# tinypico-fc.net
KiCad netlist of a schematic drawn in EAGLE
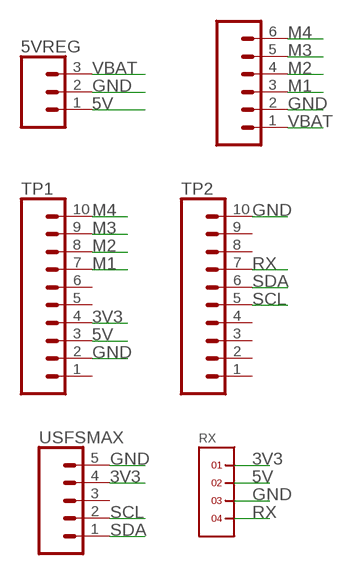
[diagram p0: schematic, sheet 1]

(export (version "E")
  (design (tool "Eeschema 10.0.6"))
  (components
    (comp (ref "5VREG")
      (value "CONN_031X03_NO_SILK")
      (footprint "eagle-import:1X03_NO_SILK")
      (libsource (lib "eagle-import") (part "CONN_031X03_NO_SILK"))
    )
    (comp (ref "ESC")
      (value "CONN_06NO_SILK_FEMALE_PTH")
      (footprint "eagle-import:1X06_NO_SILK")
      (libsource (lib "eagle-import") (part "CONN_06NO_SILK_FEMALE_PTH"))
    )
    (comp (ref "RX")
      (value "1X4")
      (footprint "eagle-import:1X4")
      (libsource (lib "eagle-import") (part "1X4"))
    )
    (comp (ref "TP1")
      (value "CONN_10NO_SILK_PTH_FEMALE")
      (footprint "eagle-import:1X10_NO_SILK")
      (libsource (lib "eagle-import") (part "CONN_10NO_SILK_PTH_FEMALE"))
    )
    (comp (ref "TP2")
      (value "CONN_10NO_SILK_PTH_FEMALE")
      (footprint "eagle-import:1X10_NO_SILK")
      (libsource (lib "eagle-import") (part "CONN_10NO_SILK_PTH_FEMALE"))
    )
    (comp (ref "USFSMAX")
      (value "CONN_05NO_SILK")
      (footprint "eagle-import:1X05_NO_SILK")
      (libsource (lib "eagle-import") (part "CONN_05NO_SILK"))
    )
  )
  (nets
    (net (code "1") (name "/3V3") (class "Default")
      (node (ref "RX") (pin "1") (pinfunction "1_1") (pintype "bidirectional"))
      (node (ref "TP1") (pin "4") (pinfunction "4_4") (pintype "passive"))
      (node (ref "USFSMAX") (pin "4") (pinfunction "4_4") (pintype "passive"))
    )
    (net (code "2") (name "/5V") (class "Default")
      (node (ref "5VREG") (pin "1") (pinfunction "1_1") (pintype "passive"))
      (node (ref "RX") (pin "2") (pinfunction "2_2") (pintype "bidirectional"))
      (node (ref "TP1") (pin "3") (pinfunction "3_3") (pintype "passive"))
    )
    (net (code "3") (name "/GND") (class "Default")
      (node (ref "5VREG") (pin "2") (pinfunction "2_2") (pintype "passive"))
      (node (ref "ESC") (pin "2") (pinfunction "2_2") (pintype "passive"))
      (node (ref "RX") (pin "3") (pinfunction "3_3") (pintype "bidirectional"))
      (node (ref "TP1") (pin "2") (pinfunction "2_2") (pintype "passive"))
      (node (ref "TP2") (pin "10") (pinfunction "10_10") (pintype "passive"))
      (node (ref "USFSMAX") (pin "5") (pinfunction "5_5") (pintype "passive"))
    )
    (net (code "4") (name "/M1") (class "Default")
      (node (ref "ESC") (pin "3") (pinfunction "3_3") (pintype "passive"))
      (node (ref "TP1") (pin "7") (pinfunction "7_7") (pintype "passive"))
    )
    (net (code "5") (name "/M2") (class "Default")
      (node (ref "ESC") (pin "4") (pinfunction "4_4") (pintype "passive"))
      (node (ref "TP1") (pin "8") (pinfunction "8_8") (pintype "passive"))
    )
    (net (code "6") (name "/M3") (class "Default")
      (node (ref "ESC") (pin "5") (pinfunction "5_5") (pintype "passive"))
      (node (ref "TP1") (pin "9") (pinfunction "9_9") (pintype "passive"))
    )
    (net (code "7") (name "/M4") (class "Default")
      (node (ref "ESC") (pin "6") (pinfunction "6_6") (pintype "passive"))
      (node (ref "TP1") (pin "10") (pinfunction "10_10") (pintype "passive"))
    )
    (net (code "8") (name "/RX") (class "Default")
      (node (ref "RX") (pin "4") (pinfunction "4_4") (pintype "bidirectional"))
      (node (ref "TP2") (pin "7") (pinfunction "7_7") (pintype "passive"))
    )
    (net (code "9") (name "/SCL") (class "Default")
      (node (ref "TP2") (pin "5") (pinfunction "5_5") (pintype "passive"))
      (node (ref "USFSMAX") (pin "2") (pinfunction "2_2") (pintype "passive"))
    )
    (net (code "10") (name "/SDA") (class "Default")
      (node (ref "TP2") (pin "6") (pinfunction "6_6") (pintype "passive"))
      (node (ref "USFSMAX") (pin "1") (pinfunction "1_1") (pintype "passive"))
    )
    (net (code "11") (name "/VBAT") (class "Default")
      (node (ref "5VREG") (pin "3") (pinfunction "3_3") (pintype "passive"))
      (node (ref "ESC") (pin "1") (pinfunction "1_1") (pintype "passive"))
    )
    (net (code "12") (name "unconnected-(TP1-Pad1)") (class "Default")
      (node (ref "TP1") (pin "1") (pinfunction "1_1") (pintype "passive"))
    )
    (net (code "13") (name "unconnected-(TP1-Pad5)") (class "Default")
      (node (ref "TP1") (pin "5") (pinfunction "5_5") (pintype "passive"))
    )
    (net (code "14") (name "unconnected-(TP1-Pad6)") (class "Default")
      (node (ref "TP1") (pin "6") (pinfunction "6_6") (pintype "passive"))
    )
    (net (code "15") (name "unconnected-(TP2-Pad1)") (class "Default")
      (node (ref "TP2") (pin "1") (pinfunction "1_1") (pintype "passive"))
    )
    (net (code "16") (name "unconnected-(TP2-Pad2)") (class "Default")
      (node (ref "TP2") (pin "2") (pinfunction "2_2") (pintype "passive"))
    )
    (net (code "17") (name "unconnected-(TP2-Pad3)") (class "Default")
      (node (ref "TP2") (pin "3") (pinfunction "3_3") (pintype "passive"))
    )
    (net (code "18") (name "unconnected-(TP2-Pad4)") (class "Default")
      (node (ref "TP2") (pin "4") (pinfunction "4_4") (pintype "passive"))
    )
    (net (code "19") (name "unconnected-(TP2-Pad8)") (class "Default")
      (node (ref "TP2") (pin "8") (pinfunction "8_8") (pintype "passive"))
    )
    (net (code "20") (name "unconnected-(TP2-Pad9)") (class "Default")
      (node (ref "TP2") (pin "9") (pinfunction "9_9") (pintype "passive"))
    )
    (net (code "21") (name "unconnected-(USFSMAX-Pad3)") (class "Default")
      (node (ref "USFSMAX") (pin "3") (pinfunction "3_3") (pintype "passive"))
    )
  )
)
